# CONNECTIONS.net
KiCad netlist of a schematic drawn in Altium Designer
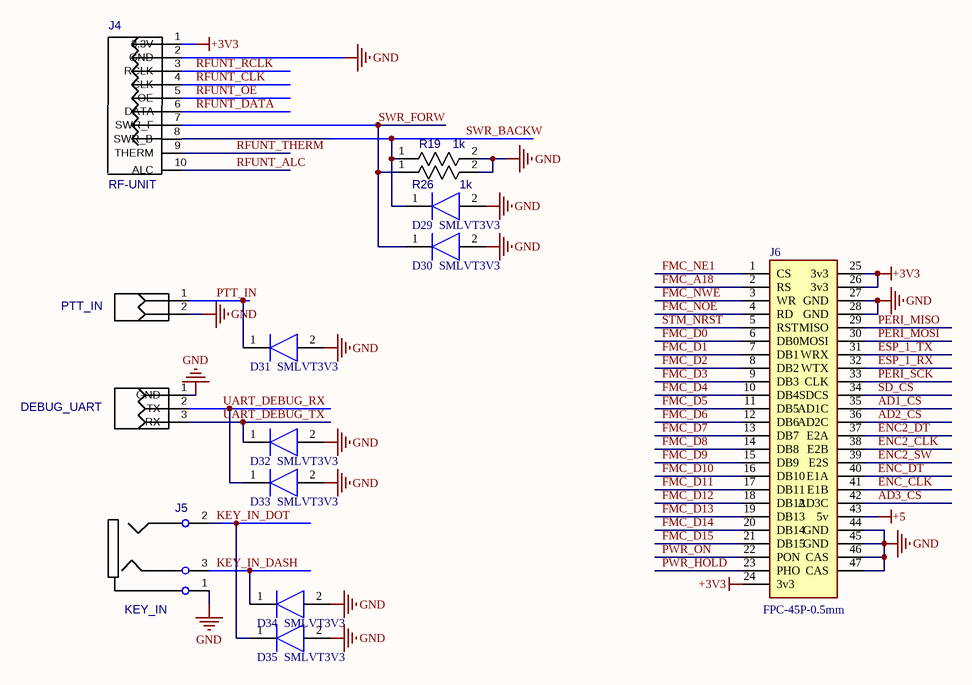
[diagram p0: CONNECTIONS.SchDoc]

(export (version "E")
  (design (tool "Eeschema 10.0.6"))
  (components
    (comp (ref "D29")
      (value "SMLVT3V3")
      (footprint "SamacSys:SMBJ36CATR")
      (description "Diode")
      (fields (field (name "MOUSER PART NUMBER") "511-SMLVT3V3") (field (name "RS PART NUMBER") "5444821P"))
      (libsource (lib "*") (part "SMLVT3V3"))
    )
    (comp (ref "D30")
      (value "SMLVT3V3")
      (footprint "SamacSys:SMBJ36CATR")
      (description "Diode")
      (fields (field (name "MOUSER PART NUMBER") "511-SMLVT3V3") (field (name "RS PART NUMBER") "5444821P"))
      (libsource (lib "*") (part "SMLVT3V3"))
    )
    (comp (ref "D31")
      (value "SMLVT3V3")
      (footprint "SamacSys:SMBJ36CATR")
      (description "Diode")
      (fields (field (name "MOUSER PART NUMBER") "511-SMLVT3V3") (field (name "RS PART NUMBER") "5444821P"))
      (libsource (lib "*") (part "SMLVT3V3"))
    )
    (comp (ref "D32")
      (value "SMLVT3V3")
      (footprint "SamacSys:SMBJ36CATR")
      (description "Diode")
      (fields (field (name "MOUSER PART NUMBER") "511-SMLVT3V3") (field (name "RS PART NUMBER") "5444821P"))
      (libsource (lib "*") (part "SMLVT3V3"))
    )
    (comp (ref "D33")
      (value "SMLVT3V3")
      (footprint "SamacSys:SMBJ36CATR")
      (description "Diode")
      (fields (field (name "MOUSER PART NUMBER") "511-SMLVT3V3") (field (name "RS PART NUMBER") "5444821P"))
      (libsource (lib "*") (part "SMLVT3V3"))
    )
    (comp (ref "D34")
      (value "SMLVT3V3")
      (footprint "SamacSys:SMBJ36CATR")
      (description "Diode")
      (fields (field (name "MOUSER PART NUMBER") "511-SMLVT3V3") (field (name "RS PART NUMBER") "5444821P"))
      (libsource (lib "*") (part "SMLVT3V3"))
    )
    (comp (ref "D35")
      (value "SMLVT3V3")
      (footprint "SamacSys:SMBJ36CATR")
      (description "Diode")
      (fields (field (name "MOUSER PART NUMBER") "511-SMLVT3V3") (field (name "RS PART NUMBER") "5444821P"))
      (libsource (lib "*") (part "SMLVT3V3"))
    )
    (comp (ref "DEBUG_UART")
      (value "DEBUG_UART")
      (footprint "51022-0300")
      (description "3 Pin")
      (libsource (lib "*") (part "51022-0300"))
    )
    (comp (ref "J4")
      (value "RF-UNIT")
      (footprint "90131-0126")
      (description "2*5 Pin")
      (libsource (lib "MOTHERBOARD") (part "90131-0126"))
    )
    (comp (ref "J5")
      (value "KEY_IN")
      (footprint "SJ1-3523N")
      (description "SJ1-3523N")
      (libsource (lib "*") (part "SJ1-3523N"))
    )
    (comp (ref "J6")
      (value "FPC-45P-0.5mm")
      (footprint "SamacSys:FH12S45S05SH60")
      (description "Connector")
      (fields
        (field (name "MANUFACTURER_PART_NUMBER") "FH12S-45S-0.5SH(55)")
        (field (name "MOUSER PART NUMBER") "798-FH12S-45S-05SH55")
      )
      (libsource (lib "*") (part "FH12S-45S-0.5SH_55_"))
    )
    (comp (ref "PTT_IN")
      (value "PTT_IN")
      (footprint "51022-0200")
      (description "51022-0200")
      (libsource (lib "*") (part "51022-0200"))
    )
    (comp (ref "R19")
      (value "1k")
      (footprint "RES_0805")
      (description "RES_0805")
      (libsource (lib "*") (part "RES_0805"))
    )
    (comp (ref "R26")
      (value "1k")
      (footprint "RES_0805")
      (description "RES_0805")
      (libsource (lib "*") (part "RES_0805"))
    )
  )
  (nets
    (net (code "1") (name "+3V3") (class "Default")
      (node (ref "J4") (pin "1") (pinfunction "3.3V_1") (pintype "passive"))
      (node (ref "J6") (pin "24") (pinfunction "3v3_24") (pintype "passive"))
      (node (ref "J6") (pin "25") (pinfunction "3v3_25") (pintype "passive"))
      (node (ref "J6") (pin "26") (pinfunction "3v3_26") (pintype "passive"))
    )
    (net (code "2") (name "+5") (class "Default")
      (node (ref "J6") (pin "43") (pinfunction "5v_43") (pintype "passive"))
    )
    (net (code "3") (name "/AD1_CS") (class "Default")
      (node (ref "J6") (pin "35") (pinfunction "AD1C_35") (pintype "passive"))
    )
    (net (code "4") (name "/AD2_CS") (class "Default")
      (node (ref "J6") (pin "36") (pinfunction "AD2C_36") (pintype "passive"))
    )
    (net (code "5") (name "/AD3_CS") (class "Default")
      (node (ref "J6") (pin "42") (pinfunction "AD3C_42") (pintype "passive"))
    )
    (net (code "6") (name "/ENC2_CLK") (class "Default")
      (node (ref "J6") (pin "38") (pinfunction "E2B_38") (pintype "passive"))
    )
    (net (code "7") (name "/ENC2_DT") (class "Default")
      (node (ref "J6") (pin "37") (pinfunction "E2A_37") (pintype "passive"))
    )
    (net (code "8") (name "/ENC2_SW") (class "Default")
      (node (ref "J6") (pin "39") (pinfunction "E2S_39") (pintype "passive"))
    )
    (net (code "9") (name "/ENC_CLK") (class "Default")
      (node (ref "J6") (pin "41") (pinfunction "E1B_41") (pintype "passive"))
    )
    (net (code "10") (name "/ENC_DT") (class "Default")
      (node (ref "J6") (pin "40") (pinfunction "E1A_40") (pintype "passive"))
    )
    (net (code "11") (name "/ESP_1_RX") (class "Default")
      (node (ref "J6") (pin "32") (pinfunction "WTX_32") (pintype "passive"))
    )
    (net (code "12") (name "/ESP_1_TX") (class "Default")
      (node (ref "J6") (pin "31") (pinfunction "WRX_31") (pintype "passive"))
    )
    (net (code "13") (name "/FMC_A18") (class "Default")
      (node (ref "J6") (pin "2") (pinfunction "RS_2") (pintype "passive"))
    )
    (net (code "14") (name "/FMC_D0") (class "Default")
      (node (ref "J6") (pin "6") (pinfunction "DB0_6") (pintype "passive"))
    )
    (net (code "15") (name "/FMC_D1") (class "Default")
      (node (ref "J6") (pin "7") (pinfunction "DB1_7") (pintype "passive"))
    )
    (net (code "16") (name "/FMC_D2") (class "Default")
      (node (ref "J6") (pin "8") (pinfunction "DB2_8") (pintype "passive"))
    )
    (net (code "17") (name "/FMC_D3") (class "Default")
      (node (ref "J6") (pin "9") (pinfunction "DB3_9") (pintype "passive"))
    )
    (net (code "18") (name "/FMC_D4") (class "Default")
      (node (ref "J6") (pin "10") (pinfunction "DB4_10") (pintype "passive"))
    )
    (net (code "19") (name "/FMC_D5") (class "Default")
      (node (ref "J6") (pin "11") (pinfunction "DB5_11") (pintype "passive"))
    )
    (net (code "20") (name "/FMC_D6") (class "Default")
      (node (ref "J6") (pin "12") (pinfunction "DB6_12") (pintype "passive"))
    )
    (net (code "21") (name "/FMC_D7") (class "Default")
      (node (ref "J6") (pin "13") (pinfunction "DB7_13") (pintype "passive"))
    )
    (net (code "22") (name "/FMC_D8") (class "Default")
      (node (ref "J6") (pin "14") (pinfunction "DB8_14") (pintype "passive"))
    )
    (net (code "23") (name "/FMC_D9") (class "Default")
      (node (ref "J6") (pin "15") (pinfunction "DB9_15") (pintype "passive"))
    )
    (net (code "24") (name "/FMC_D10") (class "Default")
      (node (ref "J6") (pin "16") (pinfunction "DB10_16") (pintype "passive"))
    )
    (net (code "25") (name "/FMC_D11") (class "Default")
      (node (ref "J6") (pin "17") (pinfunction "DB11_17") (pintype "passive"))
    )
    (net (code "26") (name "/FMC_D12") (class "Default")
      (node (ref "J6") (pin "18") (pinfunction "DB12_18") (pintype "passive"))
    )
    (net (code "27") (name "/FMC_D13") (class "Default")
      (node (ref "J6") (pin "19") (pinfunction "DB13_19") (pintype "passive"))
    )
    (net (code "28") (name "/FMC_D14") (class "Default")
      (node (ref "J6") (pin "20") (pinfunction "DB14_20") (pintype "passive"))
    )
    (net (code "29") (name "/FMC_D15") (class "Default")
      (node (ref "J6") (pin "21") (pinfunction "DB15_21") (pintype "passive"))
    )
    (net (code "30") (name "/FMC_NE1") (class "Default")
      (node (ref "J6") (pin "1") (pinfunction "CS_1") (pintype "passive"))
    )
    (net (code "31") (name "/FMC_NOE") (class "Default")
      (node (ref "J6") (pin "4") (pinfunction "RD_4") (pintype "passive"))
    )
    (net (code "32") (name "/FMC_NWE") (class "Default")
      (node (ref "J6") (pin "3") (pinfunction "WR_3") (pintype "passive"))
    )
    (net (code "33") (name "/KEY_IN_DASH") (class "Default")
      (node (ref "D34") (pin "1") (pinfunction "K_1") (pintype "passive"))
      (node (ref "J5") (pin "3") (pinfunction "ring_3") (pintype "passive"))
    )
    (net (code "34") (name "/KEY_IN_DOT") (class "Default")
      (node (ref "D35") (pin "1") (pinfunction "K_1") (pintype "passive"))
      (node (ref "J5") (pin "2") (pinfunction "tip_2") (pintype "passive"))
    )
    (net (code "35") (name "/PERI_MISO") (class "Default")
      (node (ref "J6") (pin "29") (pinfunction "MISO_29") (pintype "passive"))
    )
    (net (code "36") (name "/PERI_MOSI") (class "Default")
      (node (ref "J6") (pin "30") (pinfunction "MOSI_30") (pintype "passive"))
    )
    (net (code "37") (name "/PERI_SCK") (class "Default")
      (node (ref "J6") (pin "33") (pinfunction "CLK_33") (pintype "passive"))
    )
    (net (code "38") (name "/PTT_IN") (class "Default")
      (node (ref "D31") (pin "1") (pinfunction "K_1") (pintype "passive"))
      (node (ref "PTT_IN") (pin "1") (pinfunction "1_1") (pintype "passive"))
    )
    (net (code "39") (name "/PWR_HOLD") (class "Default")
      (node (ref "J6") (pin "23") (pinfunction "PHO_23") (pintype "passive"))
    )
    (net (code "40") (name "/PWR_ON") (class "Default")
      (node (ref "J6") (pin "22") (pinfunction "PON_22") (pintype "passive"))
    )
    (net (code "41") (name "/RFUNT_ALC") (class "Default")
      (node (ref "J4") (pin "10") (pinfunction "ALC_10") (pintype "passive"))
    )
    (net (code "42") (name "/RFUNT_CLK") (class "Default")
      (node (ref "J4") (pin "4") (pinfunction "CLK_4") (pintype "passive"))
    )
    (net (code "43") (name "/RFUNT_DATA") (class "Default")
      (node (ref "J4") (pin "6") (pinfunction "DATA_6") (pintype "passive"))
    )
    (net (code "44") (name "/RFUNT_OE") (class "Default")
      (node (ref "J4") (pin "5") (pinfunction "OE_5") (pintype "passive"))
    )
    (net (code "45") (name "/RFUNT_RCLK") (class "Default")
      (node (ref "J4") (pin "3") (pinfunction "RCLK_3") (pintype "passive"))
    )
    (net (code "46") (name "/RFUNT_THERM") (class "Default")
      (node (ref "J4") (pin "9") (pinfunction "THERM_9") (pintype "passive"))
    )
    (net (code "47") (name "/SD_CS") (class "Default")
      (node (ref "J6") (pin "34") (pinfunction "SDCS_34") (pintype "passive"))
    )
    (net (code "48") (name "/STM_NRST") (class "Default")
      (node (ref "J6") (pin "5") (pinfunction "RST_5") (pintype "passive"))
    )
    (net (code "49") (name "/SWR_BACKW") (class "Default")
      (node (ref "D29") (pin "1") (pinfunction "K_1") (pintype "passive"))
      (node (ref "J4") (pin "8") (pinfunction "SWR_B_8") (pintype "passive"))
      (node (ref "R19") (pin "1") (pinfunction "1_1") (pintype "passive"))
    )
    (net (code "50") (name "/SWR_FORW") (class "Default")
      (node (ref "D30") (pin "1") (pinfunction "K_1") (pintype "passive"))
      (node (ref "J4") (pin "7") (pinfunction "SWR_F_7") (pintype "passive"))
      (node (ref "R26") (pin "1") (pinfunction "1_1") (pintype "passive"))
    )
    (net (code "51") (name "/UART_DEBUG_RX") (class "Default")
      (node (ref "D33") (pin "1") (pinfunction "K_1") (pintype "passive"))
      (node (ref "DEBUG_UART") (pin "2") (pinfunction "TX_2") (pintype "passive"))
    )
    (net (code "52") (name "/UART_DEBUG_TX") (class "Default")
      (node (ref "D32") (pin "1") (pinfunction "K_1") (pintype "passive"))
      (node (ref "DEBUG_UART") (pin "3") (pinfunction "RX_3") (pintype "passive"))
    )
    (net (code "53") (name "GND") (class "Default")
      (node (ref "D29") (pin "2") (pinfunction "A_2") (pintype "passive"))
      (node (ref "D30") (pin "2") (pinfunction "A_2") (pintype "passive"))
      (node (ref "D31") (pin "2") (pinfunction "A_2") (pintype "passive"))
      (node (ref "D32") (pin "2") (pinfunction "A_2") (pintype "passive"))
      (node (ref "D33") (pin "2") (pinfunction "A_2") (pintype "passive"))
      (node (ref "D34") (pin "2") (pinfunction "A_2") (pintype "passive"))
      (node (ref "D35") (pin "2") (pinfunction "A_2") (pintype "passive"))
      (node (ref "DEBUG_UART") (pin "1") (pinfunction "GND_1") (pintype "passive"))
      (node (ref "J4") (pin "2") (pinfunction "GND_2") (pintype "passive"))
      (node (ref "J5") (pin "1") (pinfunction "sleeve_1") (pintype "passive"))
      (node (ref "J6") (pin "27") (pinfunction "GND_27") (pintype "passive"))
      (node (ref "J6") (pin "28") (pinfunction "GND_28") (pintype "passive"))
      (node (ref "J6") (pin "44") (pinfunction "GND_44") (pintype "passive"))
      (node (ref "J6") (pin "45") (pinfunction "GND_45") (pintype "passive"))
      (node (ref "J6") (pin "46") (pinfunction "CAS_46") (pintype "passive"))
      (node (ref "J6") (pin "47") (pinfunction "CAS_47") (pintype "passive"))
      (node (ref "PTT_IN") (pin "2") (pinfunction "2_2") (pintype "passive"))
      (node (ref "R19") (pin "2") (pinfunction "2_2") (pintype "passive"))
      (node (ref "R26") (pin "2") (pinfunction "2_2") (pintype "passive"))
    )
  )
)
